# PortArrayModule.net
KiCad netlist of a schematic drawn in EAGLE
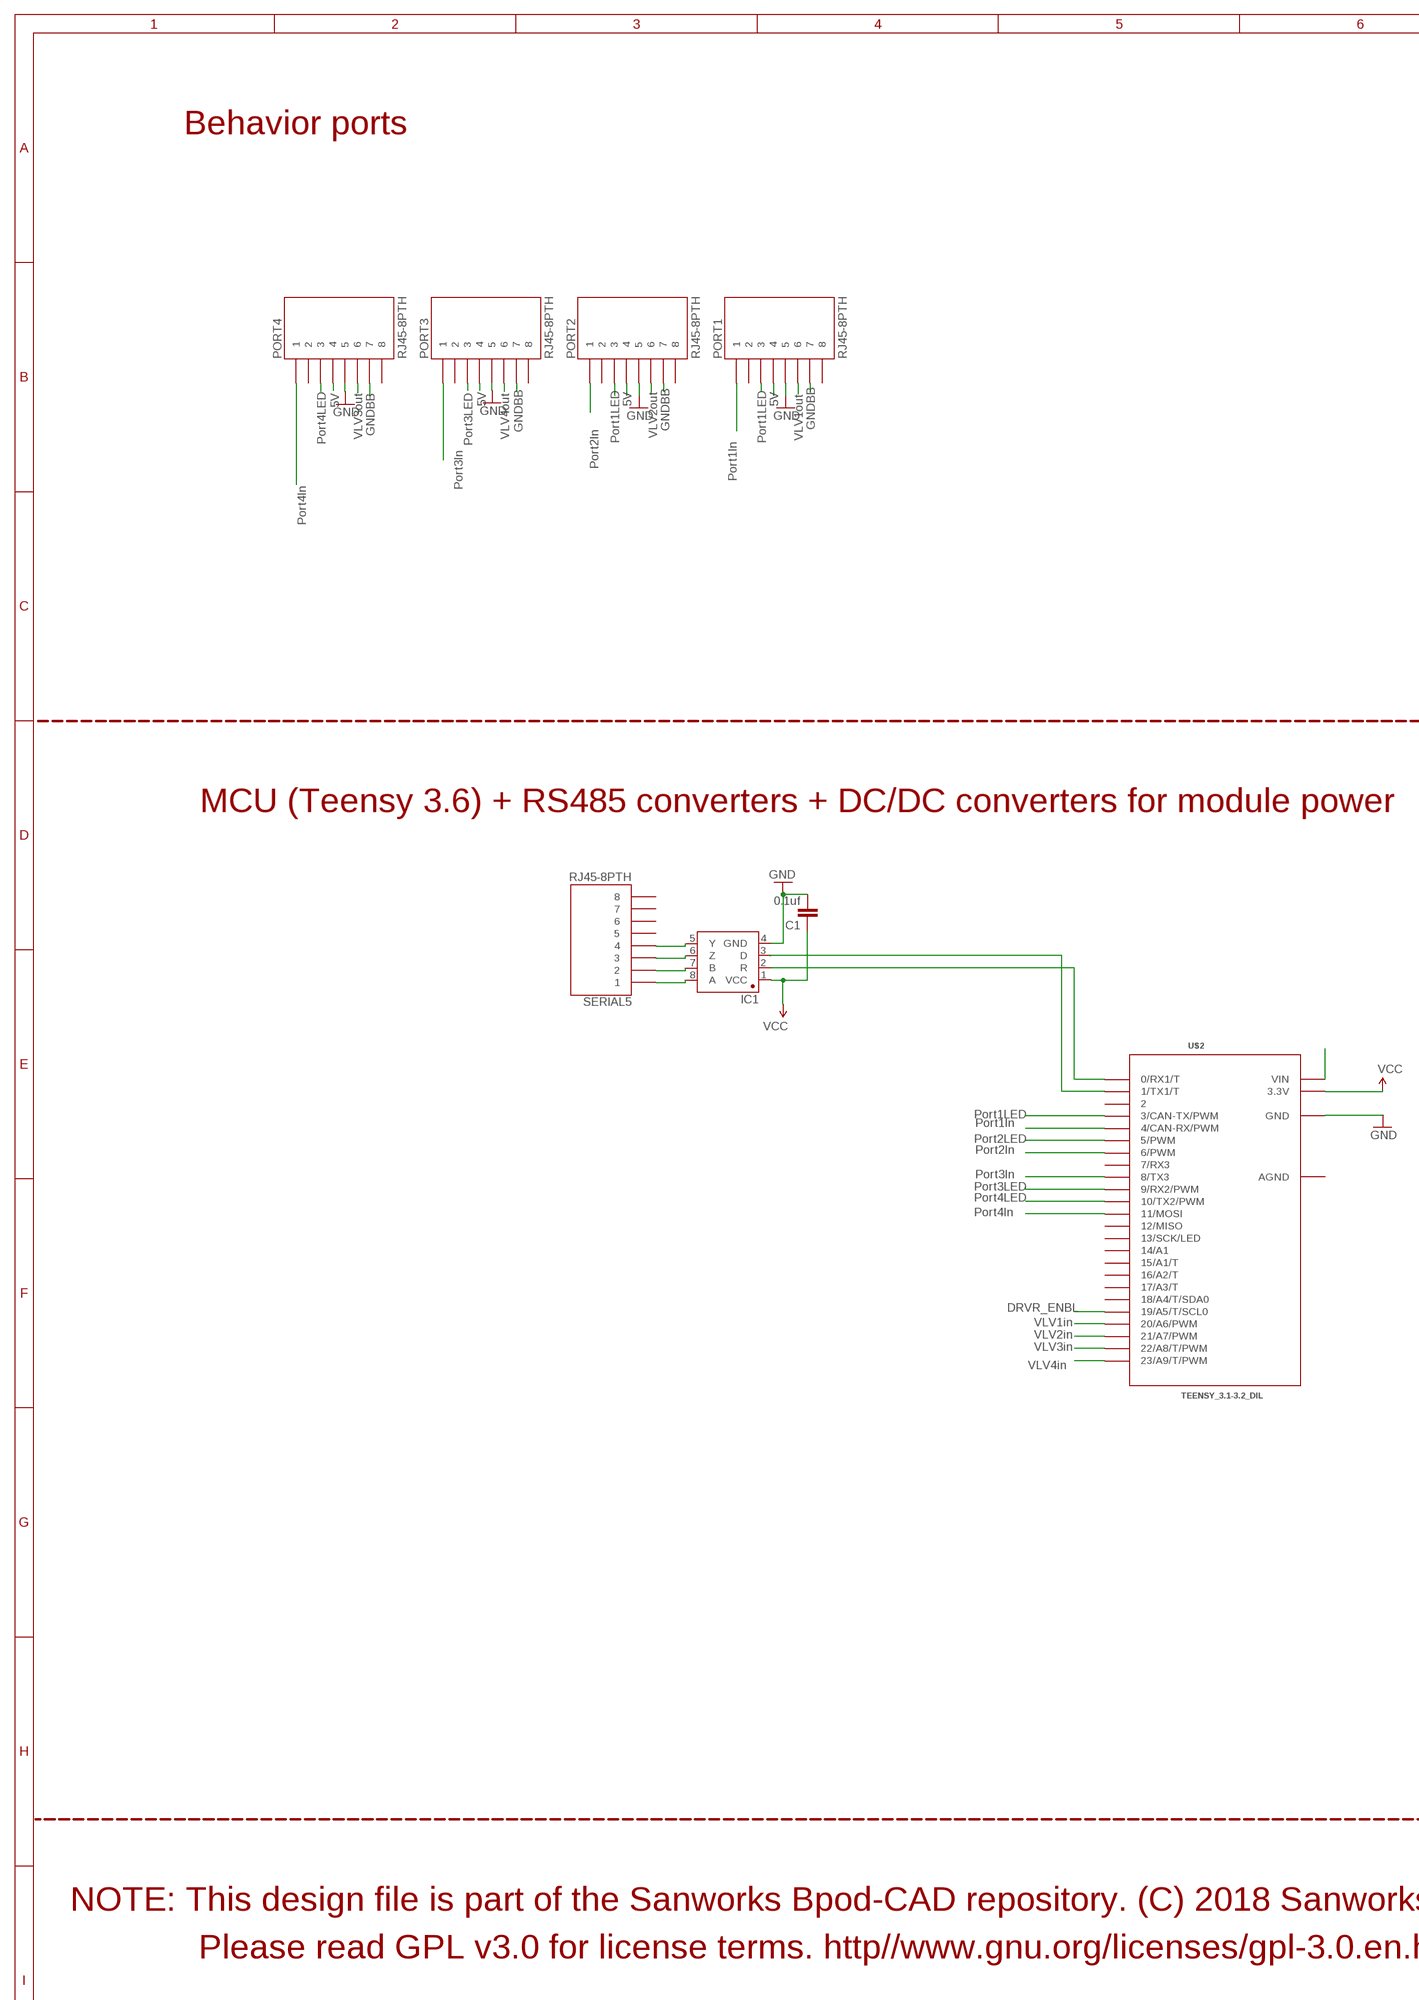
[diagram p0: schematic, sheet 1, part 1 of 2]
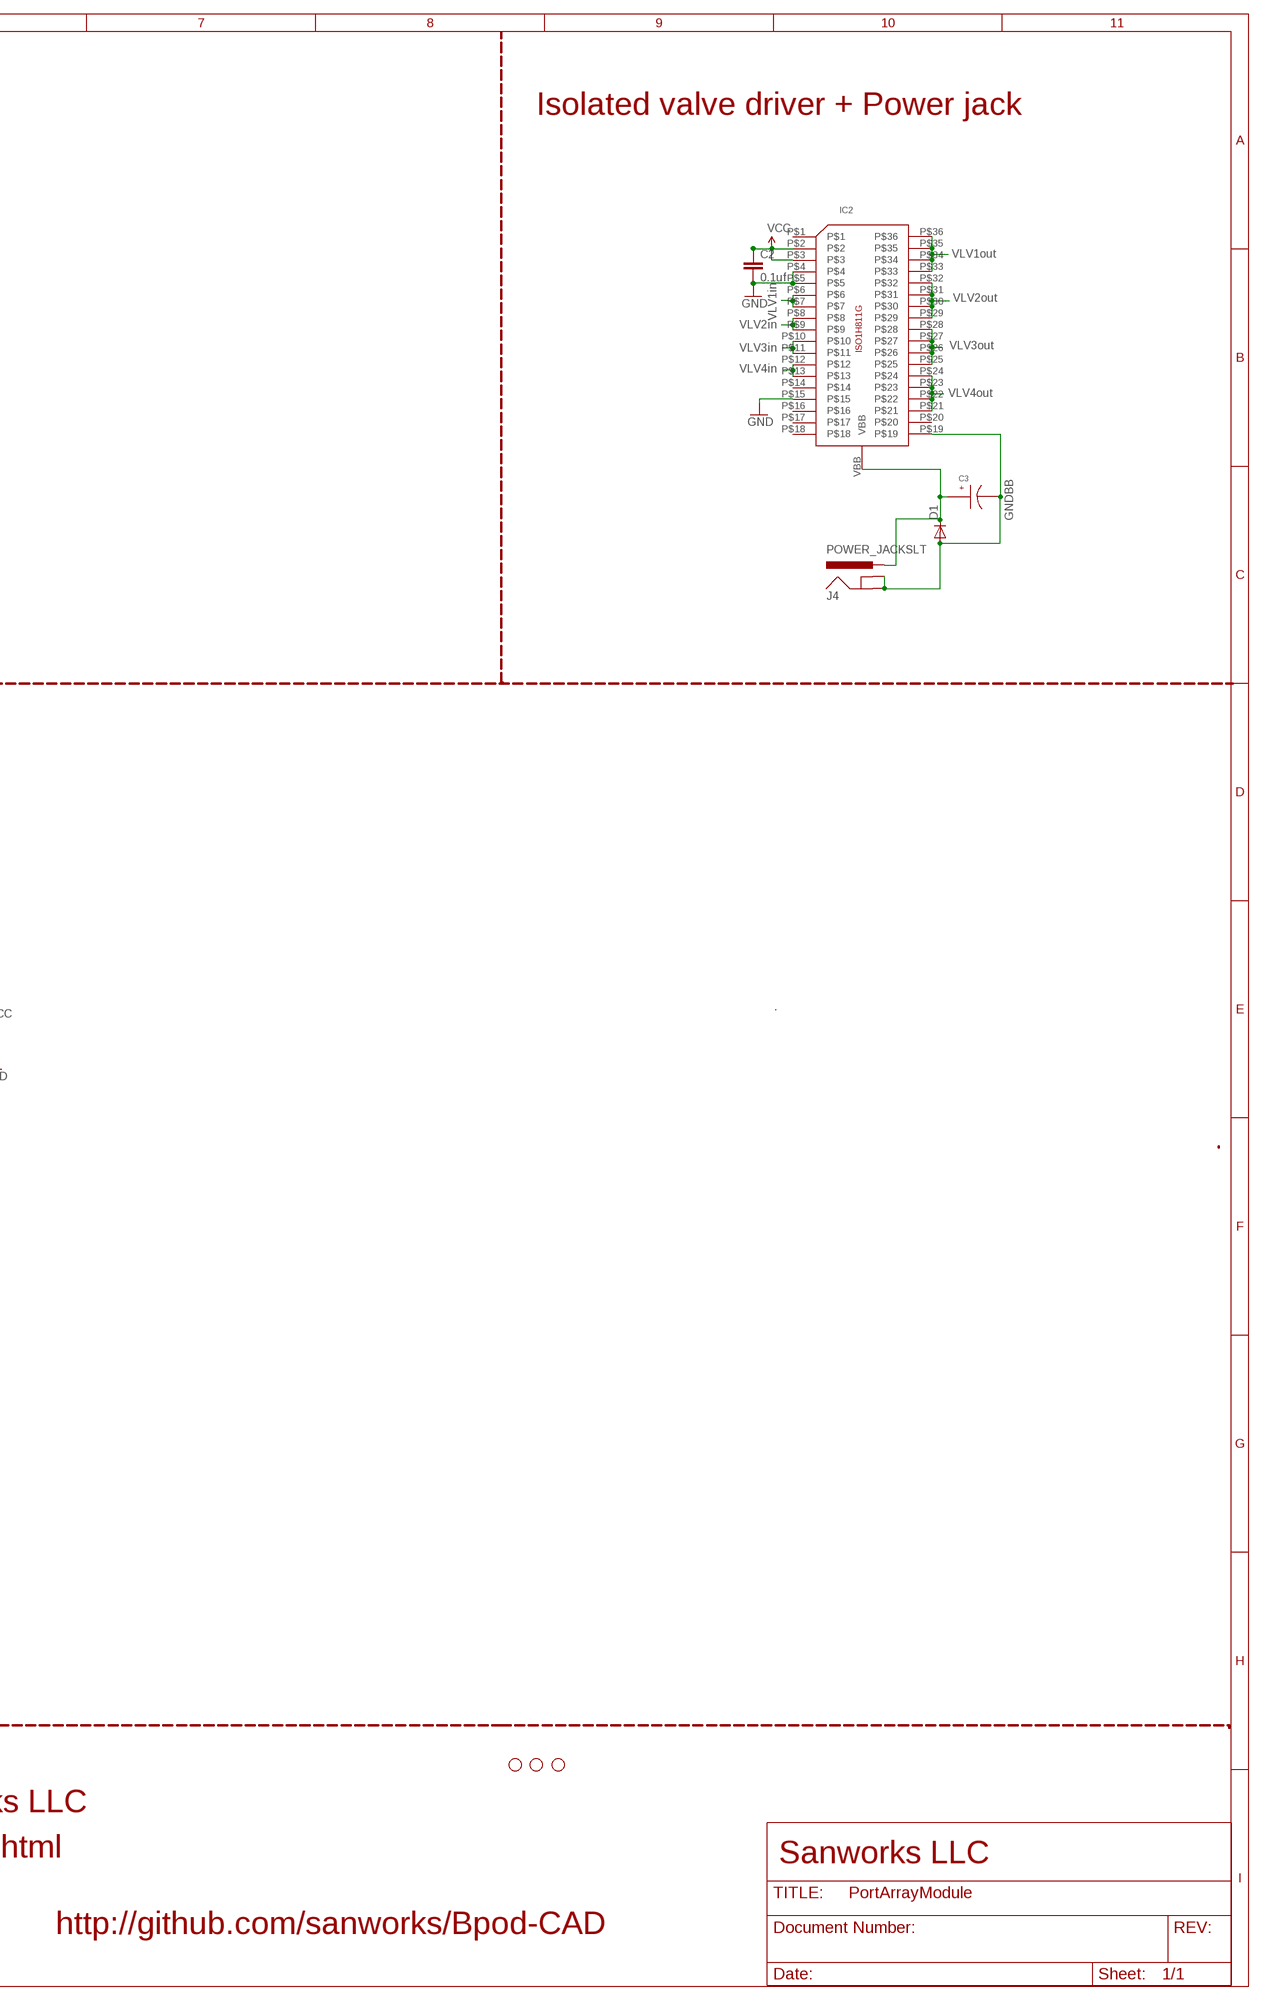
[diagram p1: schematic, sheet 1, part 2 of 2]

(export (version "E")
  (design (tool "Eeschema 10.0.6"))
  (components
    (comp (ref "C1")
      (value "0.1uf")
      (footprint "eagle-import:1206@1")
      (libsource (lib "eagle-import") (part "CAP1206"))
    )
    (comp (ref "C2")
      (value "0.1uf")
      (footprint "eagle-import:1206@1")
      (libsource (lib "eagle-import") (part "CAP1206"))
    )
    (comp (ref "C3")
      (value "EEE-FK1H100UR")
      (footprint "eagle-import:EEE-FK1H100UR")
      (libsource (lib "eagle-import") (part "EEE-FK1H100UR"))
    )
    (comp (ref "D1")
      (value "DIODE-DO214AA")
      (footprint "eagle-import:DO214AA")
      (libsource (lib "eagle-import") (part "DIODE-DO214AA"))
    )
    (comp (ref "IC1")
      (value "SN65HVD31DR")
      (footprint "eagle-import:SO08")
      (libsource (lib "eagle-import") (part "SN65HVD31DR"))
    )
    (comp (ref "IC2")
      (value "ISO1H811G")
      (footprint "eagle-import:ISO1H811G")
      (libsource (lib "eagle-import") (part "ISO1H811G"))
    )
    (comp (ref "J4")
      (value "POWER_JACKSLT")
      (footprint "eagle-import:POWER_JACK_SLOT")
      (libsource (lib "eagle-import") (part "POWER_JACKSLT"))
    )
    (comp (ref "JP3")
      (value "STAND-OFF")
      (footprint "eagle-import:STAND-OFF")
      (libsource (lib "eagle-import") (part "STAND-OFF"))
    )
    (comp (ref "JP4")
      (value "STAND-OFF")
      (footprint "eagle-import:STAND-OFF")
      (libsource (lib "eagle-import") (part "STAND-OFF"))
    )
    (comp (ref "JP5")
      (value "STAND-OFF")
      (footprint "eagle-import:STAND-OFF")
      (libsource (lib "eagle-import") (part "STAND-OFF"))
    )
    (comp (ref "PORT1")
      (value "RJ45-8PTH")
      (footprint "eagle-import:RJ45-8")
      (libsource (lib "eagle-import") (part "RJ45-8PTH"))
    )
    (comp (ref "PORT2")
      (value "RJ45-8PTH")
      (footprint "eagle-import:RJ45-8")
      (libsource (lib "eagle-import") (part "RJ45-8PTH"))
    )
    (comp (ref "PORT3")
      (value "RJ45-8PTH")
      (footprint "eagle-import:RJ45-8")
      (libsource (lib "eagle-import") (part "RJ45-8PTH"))
    )
    (comp (ref "PORT4")
      (value "RJ45-8PTH")
      (footprint "eagle-import:RJ45-8")
      (libsource (lib "eagle-import") (part "RJ45-8PTH"))
    )
    (comp (ref "SERIAL5")
      (value "RJ45-8PTH")
      (footprint "eagle-import:RJ45-8")
      (libsource (lib "eagle-import") (part "RJ45-8PTH"))
    )
    (comp (ref "U$2")
      (value "TEENSY_3.1-3.2_DIL")
      (footprint "eagle-import:TEENSY_3.0-3.2&LC_DIL")
      (libsource (lib "eagle-import") (part "TEENSY_3.1-3.2_DIL"))
    )
  )
  (nets
    (net (code "1") (name "/5V") (class "Default")
      (node (ref "PORT1") (pin "4") (pinfunction "4_4") (pintype "bidirectional"))
      (node (ref "PORT2") (pin "4") (pinfunction "4_4") (pintype "bidirectional"))
      (node (ref "PORT3") (pin "4") (pinfunction "4_4") (pintype "bidirectional"))
      (node (ref "PORT4") (pin "4") (pinfunction "4_4") (pintype "bidirectional"))
      (node (ref "U$2") (pin "VIN") (pinfunction "VIN_VIN") (pintype "power_in"))
    )
    (net (code "2") (name "/AGND") (class "Default")
      (node (ref "U$2") (pin "AGND") (pinfunction "AGND_AGND") (pintype "power_in"))
    )
    (net (code "3") (name "/GNDBB") (class "Default")
      (node (ref "C3") (pin "CATHODE") (pinfunction "CATHODE_CATHODE") (pintype "bidirectional"))
      (node (ref "D1") (pin "A") (pinfunction "A_A") (pintype "passive"))
      (node (ref "IC2") (pin "P$19") (pinfunction "P$19_P$19") (pintype "bidirectional"))
      (node (ref "J4") (pin "GND@1") (pinfunction "GNDBREAK_GND@1") (pintype "bidirectional"))
      (node (ref "J4") (pin "GND@2") (pinfunction "GND_GND@2") (pintype "bidirectional"))
      (node (ref "PORT1") (pin "7") (pinfunction "7_7") (pintype "bidirectional"))
      (node (ref "PORT2") (pin "7") (pinfunction "7_7") (pintype "bidirectional"))
      (node (ref "PORT3") (pin "7") (pinfunction "7_7") (pintype "bidirectional"))
      (node (ref "PORT4") (pin "7") (pinfunction "7_7") (pintype "bidirectional"))
    )
    (net (code "4") (name "/PORT1IN") (class "Default")
      (node (ref "PORT1") (pin "1") (pinfunction "1_1") (pintype "bidirectional"))
      (node (ref "U$2") (pin "4") (pinfunction "4/CAN-RX/PWM_4") (pintype "bidirectional"))
    )
    (net (code "5") (name "/PORT1LED") (class "Default")
      (node (ref "PORT1") (pin "3") (pinfunction "3_3") (pintype "bidirectional"))
      (node (ref "U$2") (pin "3") (pinfunction "3/CAN-TX/PWM_3") (pintype "bidirectional"))
    )
    (net (code "6") (name "/PORT2IN") (class "Default")
      (node (ref "PORT2") (pin "1") (pinfunction "1_1") (pintype "bidirectional"))
      (node (ref "U$2") (pin "6") (pinfunction "6/PWM_6") (pintype "bidirectional"))
    )
    (net (code "7") (name "/PORT2LED") (class "Default")
      (node (ref "PORT2") (pin "3") (pinfunction "3_3") (pintype "bidirectional"))
      (node (ref "U$2") (pin "5") (pinfunction "5/PWM_5") (pintype "bidirectional"))
    )
    (net (code "8") (name "/PORT3IN") (class "Default")
      (node (ref "PORT3") (pin "1") (pinfunction "1_1") (pintype "bidirectional"))
      (node (ref "U$2") (pin "8") (pinfunction "8/TX3_8") (pintype "bidirectional"))
    )
    (net (code "9") (name "/PORT3LED") (class "Default")
      (node (ref "PORT3") (pin "3") (pinfunction "3_3") (pintype "bidirectional"))
      (node (ref "U$2") (pin "9") (pinfunction "9/RX2/PWM_9") (pintype "bidirectional"))
    )
    (net (code "10") (name "/PORT4IN") (class "Default")
      (node (ref "PORT4") (pin "1") (pinfunction "1_1") (pintype "bidirectional"))
      (node (ref "U$2") (pin "11") (pinfunction "11/MOSI_11") (pintype "bidirectional"))
    )
    (net (code "11") (name "/PORT4LED") (class "Default")
      (node (ref "PORT4") (pin "3") (pinfunction "3_3") (pintype "bidirectional"))
      (node (ref "U$2") (pin "10") (pinfunction "10/TX2/PWM_10") (pintype "bidirectional"))
    )
    (net (code "12") (name "/VLV1IN") (class "Default")
      (node (ref "IC2") (pin "P$6") (pinfunction "P$6_P$6") (pintype "bidirectional"))
      (node (ref "IC2") (pin "P$7") (pinfunction "P$7_P$7") (pintype "bidirectional"))
      (node (ref "U$2") (pin "20/A6") (pinfunction "20/A6/PWM_20/A6") (pintype "bidirectional"))
    )
    (net (code "13") (name "/VLV1OUT") (class "Default")
      (node (ref "IC2") (pin "P$33") (pinfunction "P$33_P$33") (pintype "bidirectional"))
      (node (ref "IC2") (pin "P$34") (pinfunction "P$34_P$34") (pintype "bidirectional"))
      (node (ref "IC2") (pin "P$35") (pinfunction "P$35_P$35") (pintype "bidirectional"))
      (node (ref "IC2") (pin "P$36") (pinfunction "P$36_P$36") (pintype "bidirectional"))
      (node (ref "PORT1") (pin "6") (pinfunction "6_6") (pintype "bidirectional"))
    )
    (net (code "14") (name "/VLV2IN") (class "Default")
      (node (ref "IC2") (pin "P$8") (pinfunction "P$8_P$8") (pintype "bidirectional"))
      (node (ref "IC2") (pin "P$9") (pinfunction "P$9_P$9") (pintype "bidirectional"))
      (node (ref "U$2") (pin "21/A7") (pinfunction "21/A7/PWM_21/A7") (pintype "bidirectional"))
    )
    (net (code "15") (name "/VLV2OUT") (class "Default")
      (node (ref "IC2") (pin "P$29") (pinfunction "P$29_P$29") (pintype "bidirectional"))
      (node (ref "IC2") (pin "P$30") (pinfunction "P$30_P$30") (pintype "bidirectional"))
      (node (ref "IC2") (pin "P$31") (pinfunction "P$31_P$31") (pintype "bidirectional"))
      (node (ref "IC2") (pin "P$32") (pinfunction "P$32_P$32") (pintype "bidirectional"))
      (node (ref "PORT2") (pin "6") (pinfunction "6_6") (pintype "bidirectional"))
    )
    (net (code "16") (name "/VLV3IN") (class "Default")
      (node (ref "IC2") (pin "P$12") (pinfunction "P$12_P$12") (pintype "bidirectional"))
      (node (ref "IC2") (pin "P$13") (pinfunction "P$13_P$13") (pintype "bidirectional"))
      (node (ref "U$2") (pin "23/A9") (pinfunction "23/A9/T/PWM_23/A9") (pintype "bidirectional"))
    )
    (net (code "17") (name "/VLV3OUT") (class "Default")
      (node (ref "IC2") (pin "P$21") (pinfunction "P$21_P$21") (pintype "bidirectional"))
      (node (ref "IC2") (pin "P$22") (pinfunction "P$22_P$22") (pintype "bidirectional"))
      (node (ref "IC2") (pin "P$23") (pinfunction "P$23_P$23") (pintype "bidirectional"))
      (node (ref "IC2") (pin "P$24") (pinfunction "P$24_P$24") (pintype "bidirectional"))
      (node (ref "PORT3") (pin "6") (pinfunction "6_6") (pintype "bidirectional"))
    )
    (net (code "18") (name "/VLV4IN") (class "Default")
      (node (ref "IC2") (pin "P$10") (pinfunction "P$10_P$10") (pintype "bidirectional"))
      (node (ref "IC2") (pin "P$11") (pinfunction "P$11_P$11") (pintype "bidirectional"))
      (node (ref "U$2") (pin "22/A8") (pinfunction "22/A8/T/PWM_22/A8") (pintype "bidirectional"))
    )
    (net (code "19") (name "/VLV4OUT") (class "Default")
      (node (ref "IC2") (pin "P$25") (pinfunction "P$25_P$25") (pintype "bidirectional"))
      (node (ref "IC2") (pin "P$26") (pinfunction "P$26_P$26") (pintype "bidirectional"))
      (node (ref "IC2") (pin "P$27") (pinfunction "P$27_P$27") (pintype "bidirectional"))
      (node (ref "IC2") (pin "P$28") (pinfunction "P$28_P$28") (pintype "bidirectional"))
      (node (ref "PORT4") (pin "6") (pinfunction "6_6") (pintype "bidirectional"))
    )
    (net (code "20") (name "GND") (class "Default")
      (node (ref "C1") (pin "2") (pinfunction "2_2") (pintype "passive"))
      (node (ref "C2") (pin "2") (pinfunction "2_2") (pintype "passive"))
      (node (ref "IC1") (pin "4") (pinfunction "GND_4") (pintype "bidirectional"))
      (node (ref "IC2") (pin "P$15") (pinfunction "P$15_P$15") (pintype "bidirectional"))
      (node (ref "IC2") (pin "P$4") (pinfunction "P$4_P$4") (pintype "bidirectional"))
      (node (ref "IC2") (pin "P$5") (pinfunction "P$5_P$5") (pintype "bidirectional"))
      (node (ref "PORT1") (pin "5") (pinfunction "5_5") (pintype "bidirectional"))
      (node (ref "PORT2") (pin "5") (pinfunction "5_5") (pintype "bidirectional"))
      (node (ref "PORT3") (pin "5") (pinfunction "5_5") (pintype "bidirectional"))
      (node (ref "PORT4") (pin "5") (pinfunction "5_5") (pintype "bidirectional"))
      (node (ref "U$2") (pin "GND") (pinfunction "GND_GND") (pintype "power_in"))
    )
    (net (code "21") (name "Net-(C3-PadANODE)") (class "Default")
      (node (ref "C3") (pin "ANODE") (pinfunction "ANODE_ANODE") (pintype "bidirectional"))
      (node (ref "D1") (pin "C") (pinfunction "C_C") (pintype "passive"))
      (node (ref "IC2") (pin "VBB") (pinfunction "VBB_VBB") (pintype "bidirectional"))
      (node (ref "J4") (pin "PWR") (pinfunction "PWR_PWR") (pintype "bidirectional"))
    )
    (net (code "22") (name "Net-(IC1-A)") (class "Default")
      (node (ref "IC1") (pin "8") (pinfunction "A_8") (pintype "bidirectional"))
      (node (ref "SERIAL5") (pin "1") (pinfunction "1_1") (pintype "bidirectional"))
    )
    (net (code "23") (name "Net-(IC1-B)") (class "Default")
      (node (ref "IC1") (pin "7") (pinfunction "B_7") (pintype "bidirectional"))
      (node (ref "SERIAL5") (pin "2") (pinfunction "2_2") (pintype "bidirectional"))
    )
    (net (code "24") (name "Net-(IC1-D)") (class "Default")
      (node (ref "IC1") (pin "3") (pinfunction "D_3") (pintype "bidirectional"))
      (node (ref "U$2") (pin "1") (pinfunction "1/TX1/T_1") (pintype "bidirectional"))
    )
    (net (code "25") (name "Net-(IC1-R)") (class "Default")
      (node (ref "IC1") (pin "2") (pinfunction "R_2") (pintype "bidirectional"))
      (node (ref "U$2") (pin "0") (pinfunction "0/RX1/T_0") (pintype "bidirectional"))
    )
    (net (code "26") (name "Net-(IC1-Y)") (class "Default")
      (node (ref "IC1") (pin "5") (pinfunction "Y_5") (pintype "bidirectional"))
      (node (ref "SERIAL5") (pin "4") (pinfunction "4_4") (pintype "bidirectional"))
    )
    (net (code "27") (name "Net-(IC1-Z)") (class "Default")
      (node (ref "IC1") (pin "6") (pinfunction "Z_6") (pintype "bidirectional"))
      (node (ref "SERIAL5") (pin "3") (pinfunction "3_3") (pintype "bidirectional"))
    )
    (net (code "28") (name "VCC") (class "Default")
      (node (ref "C1") (pin "1") (pinfunction "1_1") (pintype "passive"))
      (node (ref "C2") (pin "1") (pinfunction "1_1") (pintype "passive"))
      (node (ref "IC1") (pin "1") (pinfunction "VCC_1") (pintype "bidirectional"))
      (node (ref "IC2") (pin "P$2") (pinfunction "P$2_P$2") (pintype "bidirectional"))
      (node (ref "IC2") (pin "P$3") (pinfunction "P$3_P$3") (pintype "bidirectional"))
      (node (ref "U$2") (pin "3.3V") (pinfunction "3.3V_3.3V") (pintype "power_in"))
    )
    (net (code "29") (name "unconnected-(IC2-PadP$1)") (class "Default")
      (node (ref "IC2") (pin "P$1") (pinfunction "P$1_P$1") (pintype "bidirectional"))
    )
    (net (code "30") (name "unconnected-(IC2-PadP$14)") (class "Default")
      (node (ref "IC2") (pin "P$14") (pinfunction "P$14_P$14") (pintype "bidirectional"))
    )
    (net (code "31") (name "unconnected-(IC2-PadP$16)") (class "Default")
      (node (ref "IC2") (pin "P$16") (pinfunction "P$16_P$16") (pintype "bidirectional"))
    )
    (net (code "32") (name "unconnected-(IC2-PadP$17)") (class "Default")
      (node (ref "IC2") (pin "P$17") (pinfunction "P$17_P$17") (pintype "bidirectional"))
    )
    (net (code "33") (name "unconnected-(IC2-PadP$18)") (class "Default")
      (node (ref "IC2") (pin "P$18") (pinfunction "P$18_P$18") (pintype "bidirectional"))
    )
    (net (code "34") (name "unconnected-(IC2-PadP$20)") (class "Default")
      (node (ref "IC2") (pin "P$20") (pinfunction "P$20_P$20") (pintype "bidirectional"))
    )
    (net (code "35") (name "unconnected-(PORT1-Pad2)") (class "Default")
      (node (ref "PORT1") (pin "2") (pinfunction "2_2") (pintype "bidirectional"))
    )
    (net (code "36") (name "unconnected-(PORT1-Pad8)") (class "Default")
      (node (ref "PORT1") (pin "8") (pinfunction "8_8") (pintype "bidirectional"))
    )
    (net (code "37") (name "unconnected-(PORT2-Pad2)") (class "Default")
      (node (ref "PORT2") (pin "2") (pinfunction "2_2") (pintype "bidirectional"))
    )
    (net (code "38") (name "unconnected-(PORT2-Pad8)") (class "Default")
      (node (ref "PORT2") (pin "8") (pinfunction "8_8") (pintype "bidirectional"))
    )
    (net (code "39") (name "unconnected-(PORT3-Pad2)") (class "Default")
      (node (ref "PORT3") (pin "2") (pinfunction "2_2") (pintype "bidirectional"))
    )
    (net (code "40") (name "unconnected-(PORT3-Pad8)") (class "Default")
      (node (ref "PORT3") (pin "8") (pinfunction "8_8") (pintype "bidirectional"))
    )
    (net (code "41") (name "unconnected-(PORT4-Pad2)") (class "Default")
      (node (ref "PORT4") (pin "2") (pinfunction "2_2") (pintype "bidirectional"))
    )
    (net (code "42") (name "unconnected-(PORT4-Pad8)") (class "Default")
      (node (ref "PORT4") (pin "8") (pinfunction "8_8") (pintype "bidirectional"))
    )
    (net (code "43") (name "unconnected-(SERIAL5-Pad5)") (class "Default")
      (node (ref "SERIAL5") (pin "5") (pinfunction "5_5") (pintype "bidirectional"))
    )
    (net (code "44") (name "unconnected-(SERIAL5-Pad6)") (class "Default")
      (node (ref "SERIAL5") (pin "6") (pinfunction "6_6") (pintype "bidirectional"))
    )
    (net (code "45") (name "unconnected-(SERIAL5-Pad7)") (class "Default")
      (node (ref "SERIAL5") (pin "7") (pinfunction "7_7") (pintype "bidirectional"))
    )
    (net (code "46") (name "unconnected-(SERIAL5-Pad8)") (class "Default")
      (node (ref "SERIAL5") (pin "8") (pinfunction "8_8") (pintype "bidirectional"))
    )
    (net (code "47") (name "unconnected-(U$2-7{slash}RX3-Pad7)") (class "Default")
      (node (ref "U$2") (pin "7") (pinfunction "7/RX3_7") (pintype "bidirectional"))
    )
    (net (code "48") (name "unconnected-(U$2-12{slash}MISO-Pad12)") (class "Default")
      (node (ref "U$2") (pin "12") (pinfunction "12/MISO_12") (pintype "bidirectional"))
    )
    (net (code "49") (name "unconnected-(U$2-13{slash}SCK{slash}LED-Pad13)") (class "Default")
      (node (ref "U$2") (pin "13") (pinfunction "13/SCK/LED_13") (pintype "bidirectional"))
    )
    (net (code "50") (name "unconnected-(U$2-14{slash}A1-Pad14{slash}A0)") (class "Default")
      (node (ref "U$2") (pin "14/A0") (pinfunction "14/A1_14/A0") (pintype "bidirectional"))
    )
    (net (code "51") (name "unconnected-(U$2-15{slash}A1{slash}T-Pad15{slash}A1)") (class "Default")
      (node (ref "U$2") (pin "15/A1") (pinfunction "15/A1/T_15/A1") (pintype "bidirectional"))
    )
    (net (code "52") (name "unconnected-(U$2-16{slash}A2{slash}T-Pad16{slash}A2)") (class "Default")
      (node (ref "U$2") (pin "16/A2") (pinfunction "16/A2/T_16/A2") (pintype "bidirectional"))
    )
    (net (code "53") (name "unconnected-(U$2-17{slash}A3{slash}T-Pad17{slash}A3)") (class "Default")
      (node (ref "U$2") (pin "17/A3") (pinfunction "17/A3/T_17/A3") (pintype "bidirectional"))
    )
    (net (code "54") (name "unconnected-(U$2-18{slash}A4{slash}T{slash}SDA0-Pad18{slash}A4)") (class "Default")
      (node (ref "U$2") (pin "18/A4") (pinfunction "18/A4/T/SDA0_18/A4") (pintype "bidirectional"))
    )
    (net (code "55") (name "unconnected-(U$2-19{slash}A5{slash}T{slash}SCL0-Pad19{slash}A5)") (class "Default")
      (node (ref "U$2") (pin "19/A5") (pinfunction "19/A5/T/SCL0_19/A5") (pintype "bidirectional"))
    )
    (net (code "56") (name "unconnected-(U$2-Pad2)") (class "Default")
      (node (ref "U$2") (pin "2") (pinfunction "2_2") (pintype "bidirectional"))
    )
  )
)
